# amp_tda2030a_v_1_0.net
KiCad netlist of a schematic drawn in EAGLE
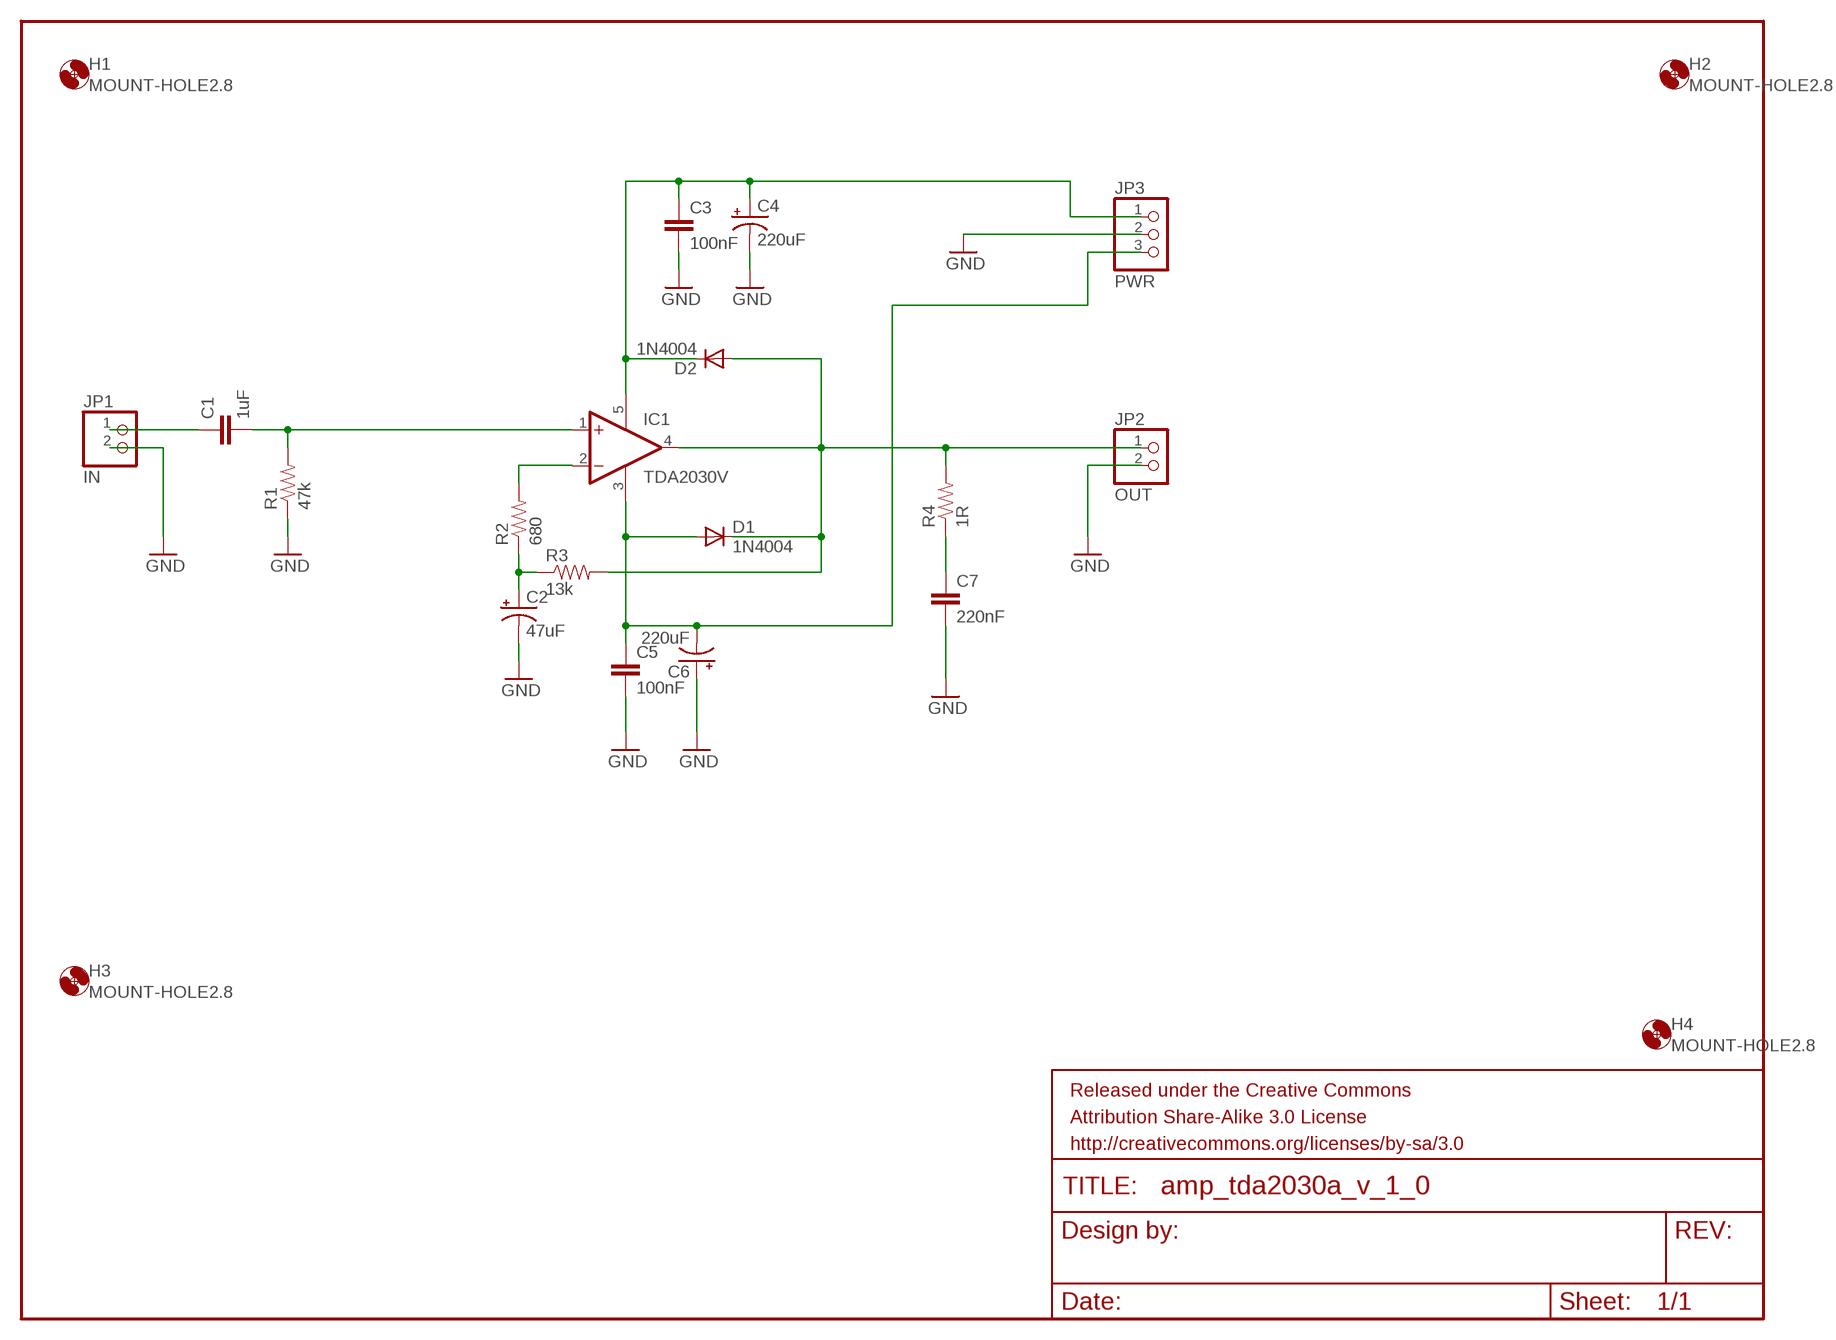
[diagram p0: schematic, sheet 1]

(export (version "E")
  (design (tool "Eeschema 10.0.6"))
  (components
    (comp (ref "C1")
      (value "1uF")
      (footprint "eagle-import:CAP-PTH-LARGE")
      (libsource (lib "eagle-import") (part "CAPPTH3"))
    )
    (comp (ref "C2")
      (value "47uF")
      (footprint "eagle-import:CPOL-RADIAL-100UF-25V")
      (libsource (lib "eagle-import") (part "CAP_POLPTH1"))
    )
    (comp (ref "C3")
      (value "100nF")
      (footprint "eagle-import:CAP-PTH-5MM")
      (libsource (lib "eagle-import") (part "CAPPTH1"))
    )
    (comp (ref "C4")
      (value "220uF")
      (footprint "eagle-import:CPOL-RADIAL-100UF-25V")
      (libsource (lib "eagle-import") (part "CAP_POLPTH1"))
    )
    (comp (ref "C5")
      (value "100nF")
      (footprint "eagle-import:CAP-PTH-5MM")
      (libsource (lib "eagle-import") (part "CAPPTH1"))
    )
    (comp (ref "C6")
      (value "220uF")
      (footprint "eagle-import:CPOL-RADIAL-100UF-25V")
      (libsource (lib "eagle-import") (part "CAP_POLPTH1"))
    )
    (comp (ref "C7")
      (value "220nF")
      (footprint "eagle-import:CAP-PTH-LARGE")
      (libsource (lib "eagle-import") (part "SparkFun-Passives_CAPPTH3"))
    )
    (comp (ref "D1")
      (value "1N4004")
      (footprint "eagle-import:DO41-10")
      (libsource (lib "eagle-import") (part "1N4004"))
    )
    (comp (ref "D2")
      (value "1N4004")
      (footprint "eagle-import:DO41-10")
      (libsource (lib "eagle-import") (part "1N4004"))
    )
    (comp (ref "FRAME1")
      (value "FRAME-LETTER")
      (footprint "eagle-import:CREATIVE_COMMONS")
      (libsource (lib "eagle-import") (part "FRAME-LETTER"))
    )
    (comp (ref "H1")
      (value "MOUNT-HOLE2.8")
      (footprint "eagle-import:2,8")
      (libsource (lib "eagle-import") (part "MOUNT-HOLE2.8"))
    )
    (comp (ref "H2")
      (value "MOUNT-HOLE2.8")
      (footprint "eagle-import:2,8")
      (libsource (lib "eagle-import") (part "MOUNT-HOLE2.8"))
    )
    (comp (ref "H3")
      (value "MOUNT-HOLE2.8")
      (footprint "eagle-import:2,8")
      (libsource (lib "eagle-import") (part "MOUNT-HOLE2.8"))
    )
    (comp (ref "H4")
      (value "MOUNT-HOLE2.8")
      (footprint "eagle-import:2,8")
      (libsource (lib "eagle-import") (part "MOUNT-HOLE2.8"))
    )
    (comp (ref "IC1")
      (value "TDA2030V")
      (footprint "eagle-import:CB360")
      (libsource (lib "eagle-import") (part "TDA2030V"))
    )
    (comp (ref "JP1")
      (value "IN")
      (footprint "eagle-import:1X02")
      (libsource (lib "eagle-import") (part "PINHD-1X2"))
    )
    (comp (ref "JP2")
      (value "OUT")
      (footprint "eagle-import:1X02")
      (libsource (lib "eagle-import") (part "PINHD-1X2"))
    )
    (comp (ref "JP3")
      (value "PWR")
      (footprint "eagle-import:1X03")
      (libsource (lib "eagle-import") (part "PINHD-1X3"))
    )
    (comp (ref "R1")
      (value "47k")
      (footprint "eagle-import:AXIAL-0.4")
      (libsource (lib "eagle-import") (part "RESISTORPTH-1/4W"))
    )
    (comp (ref "R2")
      (value "680")
      (footprint "eagle-import:AXIAL-0.4")
      (libsource (lib "eagle-import") (part "RESISTORPTH-1/4W"))
    )
    (comp (ref "R3")
      (value "13k")
      (footprint "eagle-import:AXIAL-0.4")
      (libsource (lib "eagle-import") (part "RESISTORPTH-1/4W"))
    )
    (comp (ref "R4")
      (value "1R")
      (footprint "eagle-import:AXIAL-0.4")
      (libsource (lib "eagle-import") (part "RESISTORPTH-1/4W"))
    )
  )
  (nets
    (net (code "1") (name "GND") (class "Default")
      (node (ref "C2") (pin "2") (pinfunction "-_2") (pintype "passive"))
      (node (ref "C3") (pin "2") (pinfunction "2_2") (pintype "passive"))
      (node (ref "C4") (pin "2") (pinfunction "-_2") (pintype "passive"))
      (node (ref "C5") (pin "2") (pinfunction "2_2") (pintype "passive"))
      (node (ref "C6") (pin "1") (pinfunction "+_1") (pintype "passive"))
      (node (ref "C7") (pin "2") (pinfunction "2_2") (pintype "passive"))
      (node (ref "JP1") (pin "2") (pinfunction "2_2") (pintype "passive"))
      (node (ref "JP2") (pin "2") (pinfunction "2_2") (pintype "passive"))
      (node (ref "JP3") (pin "2") (pinfunction "2_2") (pintype "passive"))
      (node (ref "R1") (pin "P$1") (pinfunction "1_P$1") (pintype "passive"))
    )
    (net (code "2") (name "Net-(C1-Pad1)") (class "Default")
      (node (ref "C1") (pin "1") (pinfunction "1_1") (pintype "passive"))
      (node (ref "JP1") (pin "1") (pinfunction "1_1") (pintype "passive"))
    )
    (net (code "3") (name "Net-(C2-+)") (class "Default")
      (node (ref "C2") (pin "1") (pinfunction "+_1") (pintype "passive"))
      (node (ref "R2") (pin "P$1") (pinfunction "1_P$1") (pintype "passive"))
      (node (ref "R3") (pin "P$1") (pinfunction "1_P$1") (pintype "passive"))
    )
    (net (code "4") (name "Net-(C4-+)") (class "Default")
      (node (ref "C3") (pin "1") (pinfunction "1_1") (pintype "passive"))
      (node (ref "C4") (pin "1") (pinfunction "+_1") (pintype "passive"))
      (node (ref "D2") (pin "C") (pinfunction "C_C") (pintype "passive"))
      (node (ref "IC1") (pin "5") (pinfunction "V+_5") (pintype "power_in"))
      (node (ref "JP3") (pin "1") (pinfunction "1_1") (pintype "passive"))
    )
    (net (code "5") (name "Net-(C6--)") (class "Default")
      (node (ref "C5") (pin "1") (pinfunction "1_1") (pintype "passive"))
      (node (ref "C6") (pin "2") (pinfunction "-_2") (pintype "passive"))
      (node (ref "D1") (pin "A") (pinfunction "A_A") (pintype "passive"))
      (node (ref "IC1") (pin "3") (pinfunction "GND_3") (pintype "power_in"))
      (node (ref "JP3") (pin "3") (pinfunction "3_3") (pintype "passive"))
    )
    (net (code "6") (name "Net-(IC1-+IN)") (class "Default")
      (node (ref "C1") (pin "2") (pinfunction "2_2") (pintype "passive"))
      (node (ref "IC1") (pin "1") (pinfunction "+IN_1") (pintype "input"))
      (node (ref "R1") (pin "P$2") (pinfunction "2_P$2") (pintype "passive"))
    )
    (net (code "7") (name "Net-(IC1--IN)") (class "Default")
      (node (ref "IC1") (pin "2") (pinfunction "-IN_2") (pintype "input"))
      (node (ref "R2") (pin "P$2") (pinfunction "2_P$2") (pintype "passive"))
    )
    (net (code "8") (name "Net-(IC1-OUT)") (class "Default")
      (node (ref "D1") (pin "C") (pinfunction "C_C") (pintype "passive"))
      (node (ref "D2") (pin "A") (pinfunction "A_A") (pintype "passive"))
      (node (ref "IC1") (pin "4") (pinfunction "OUT_4") (pintype "output"))
      (node (ref "JP2") (pin "1") (pinfunction "1_1") (pintype "passive"))
      (node (ref "R3") (pin "P$2") (pinfunction "2_P$2") (pintype "passive"))
      (node (ref "R4") (pin "P$2") (pinfunction "2_P$2") (pintype "passive"))
    )
    (net (code "9") (name "Net-(R4-1)") (class "Default")
      (node (ref "C7") (pin "1") (pinfunction "1_1") (pintype "passive"))
      (node (ref "R4") (pin "P$1") (pinfunction "1_P$1") (pintype "passive"))
    )
  )
)
